# delay_panel.net
KiCad netlist of a schematic drawn in EAGLE
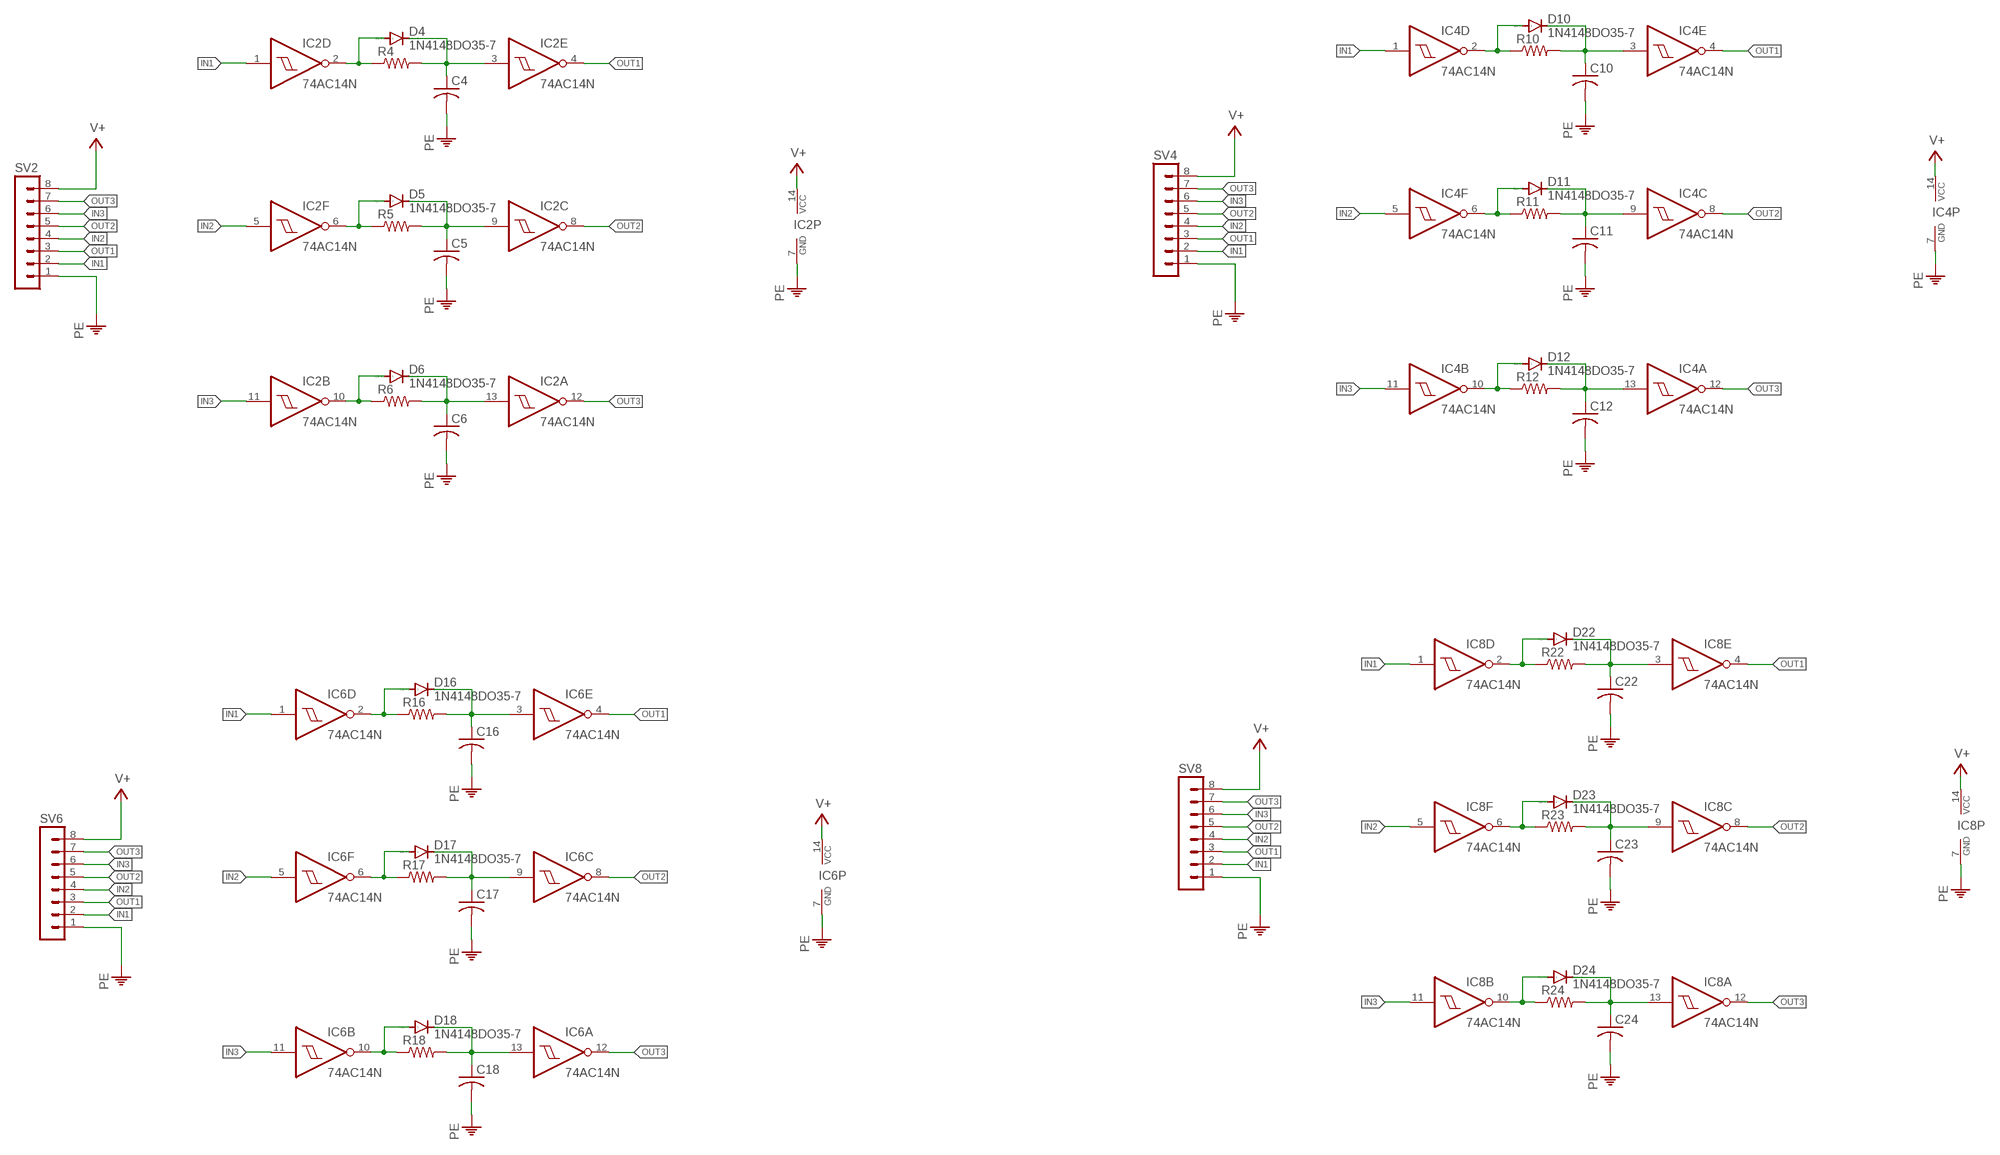
[diagram p0: schematic, sheet 1]

(export (version "E")
  (design (tool "Eeschema 10.0.6"))
  (components
    (comp (ref "C4")
      (value "C-US025-025X050")
      (footprint "eagle-import:C025-025X050")
      (libsource (lib "eagle-import") (part "C-US025-025X050"))
    )
    (comp (ref "C5")
      (value "C-US025-025X050")
      (footprint "eagle-import:C025-025X050")
      (libsource (lib "eagle-import") (part "C-US025-025X050"))
    )
    (comp (ref "C6")
      (value "C-US025-025X050")
      (footprint "eagle-import:C025-025X050")
      (libsource (lib "eagle-import") (part "C-US025-025X050"))
    )
    (comp (ref "C10")
      (value "C-US025-025X050")
      (footprint "eagle-import:C025-025X050")
      (libsource (lib "eagle-import") (part "C-US025-025X050"))
    )
    (comp (ref "C11")
      (value "C-US025-025X050")
      (footprint "eagle-import:C025-025X050")
      (libsource (lib "eagle-import") (part "C-US025-025X050"))
    )
    (comp (ref "C12")
      (value "C-US025-025X050")
      (footprint "eagle-import:C025-025X050")
      (libsource (lib "eagle-import") (part "C-US025-025X050"))
    )
    (comp (ref "C16")
      (value "C-US025-025X050")
      (footprint "eagle-import:C025-025X050")
      (libsource (lib "eagle-import") (part "C-US025-025X050"))
    )
    (comp (ref "C17")
      (value "C-US025-025X050")
      (footprint "eagle-import:C025-025X050")
      (libsource (lib "eagle-import") (part "C-US025-025X050"))
    )
    (comp (ref "C18")
      (value "C-US025-025X050")
      (footprint "eagle-import:C025-025X050")
      (libsource (lib "eagle-import") (part "C-US025-025X050"))
    )
    (comp (ref "C22")
      (value "C-US025-025X050")
      (footprint "eagle-import:C025-025X050")
      (libsource (lib "eagle-import") (part "C-US025-025X050"))
    )
    (comp (ref "C23")
      (value "C-US025-025X050")
      (footprint "eagle-import:C025-025X050")
      (libsource (lib "eagle-import") (part "C-US025-025X050"))
    )
    (comp (ref "C24")
      (value "C-US025-025X050")
      (footprint "eagle-import:C025-025X050")
      (libsource (lib "eagle-import") (part "C-US025-025X050"))
    )
    (comp (ref "D4")
      (value "1N4148DO35-7")
      (footprint "eagle-import:DO35-7")
      (libsource (lib "eagle-import") (part "1N4148DO35-7"))
    )
    (comp (ref "D5")
      (value "1N4148DO35-7")
      (footprint "eagle-import:DO35-7")
      (libsource (lib "eagle-import") (part "1N4148DO35-7"))
    )
    (comp (ref "D6")
      (value "1N4148DO35-7")
      (footprint "eagle-import:DO35-7")
      (libsource (lib "eagle-import") (part "1N4148DO35-7"))
    )
    (comp (ref "D10")
      (value "1N4148DO35-7")
      (footprint "eagle-import:DO35-7")
      (libsource (lib "eagle-import") (part "1N4148DO35-7"))
    )
    (comp (ref "D11")
      (value "1N4148DO35-7")
      (footprint "eagle-import:DO35-7")
      (libsource (lib "eagle-import") (part "1N4148DO35-7"))
    )
    (comp (ref "D12")
      (value "1N4148DO35-7")
      (footprint "eagle-import:DO35-7")
      (libsource (lib "eagle-import") (part "1N4148DO35-7"))
    )
    (comp (ref "D16")
      (value "1N4148DO35-7")
      (footprint "eagle-import:DO35-7")
      (libsource (lib "eagle-import") (part "1N4148DO35-7"))
    )
    (comp (ref "D17")
      (value "1N4148DO35-7")
      (footprint "eagle-import:DO35-7")
      (libsource (lib "eagle-import") (part "1N4148DO35-7"))
    )
    (comp (ref "D18")
      (value "1N4148DO35-7")
      (footprint "eagle-import:DO35-7")
      (libsource (lib "eagle-import") (part "1N4148DO35-7"))
    )
    (comp (ref "D22")
      (value "1N4148DO35-7")
      (footprint "eagle-import:DO35-7")
      (libsource (lib "eagle-import") (part "1N4148DO35-7"))
    )
    (comp (ref "D23")
      (value "1N4148DO35-7")
      (footprint "eagle-import:DO35-7")
      (libsource (lib "eagle-import") (part "1N4148DO35-7"))
    )
    (comp (ref "D24")
      (value "1N4148DO35-7")
      (footprint "eagle-import:DO35-7")
      (libsource (lib "eagle-import") (part "1N4148DO35-7"))
    )
    (comp (ref "IC2")
      (value "74AC14N")
      (footprint "eagle-import:DIL14")
      (libsource (lib "eagle-import") (part "7414NAC"))
    )
    (comp (ref "IC4")
      (value "74AC14N")
      (footprint "eagle-import:DIL14")
      (libsource (lib "eagle-import") (part "7414NAC"))
    )
    (comp (ref "IC6")
      (value "74AC14N")
      (footprint "eagle-import:DIL14")
      (libsource (lib "eagle-import") (part "7414NAC"))
    )
    (comp (ref "IC8")
      (value "74AC14N")
      (footprint "eagle-import:DIL14")
      (libsource (lib "eagle-import") (part "7414NAC"))
    )
    (comp (ref "R4")
      (value "R-US_0204/7")
      (footprint "eagle-import:0204_7")
      (libsource (lib "eagle-import") (part "R-US_0204/7"))
    )
    (comp (ref "R5")
      (value "R-US_0204/7")
      (footprint "eagle-import:0204_7")
      (libsource (lib "eagle-import") (part "R-US_0204/7"))
    )
    (comp (ref "R6")
      (value "R-US_0204/7")
      (footprint "eagle-import:0204_7")
      (libsource (lib "eagle-import") (part "R-US_0204/7"))
    )
    (comp (ref "R10")
      (value "R-US_0204/7")
      (footprint "eagle-import:0204_7")
      (libsource (lib "eagle-import") (part "R-US_0204/7"))
    )
    (comp (ref "R11")
      (value "R-US_0204/7")
      (footprint "eagle-import:0204_7")
      (libsource (lib "eagle-import") (part "R-US_0204/7"))
    )
    (comp (ref "R12")
      (value "R-US_0204/7")
      (footprint "eagle-import:0204_7")
      (libsource (lib "eagle-import") (part "R-US_0204/7"))
    )
    (comp (ref "R16")
      (value "R-US_0204/7")
      (footprint "eagle-import:0204_7")
      (libsource (lib "eagle-import") (part "R-US_0204/7"))
    )
    (comp (ref "R17")
      (value "R-US_0204/7")
      (footprint "eagle-import:0204_7")
      (libsource (lib "eagle-import") (part "R-US_0204/7"))
    )
    (comp (ref "R18")
      (value "R-US_0204/7")
      (footprint "eagle-import:0204_7")
      (libsource (lib "eagle-import") (part "R-US_0204/7"))
    )
    (comp (ref "R22")
      (value "R-US_0204/7")
      (footprint "eagle-import:0204_7")
      (libsource (lib "eagle-import") (part "R-US_0204/7"))
    )
    (comp (ref "R23")
      (value "R-US_0204/7")
      (footprint "eagle-import:0204_7")
      (libsource (lib "eagle-import") (part "R-US_0204/7"))
    )
    (comp (ref "R24")
      (value "R-US_0204/7")
      (footprint "eagle-import:0204_7")
      (libsource (lib "eagle-import") (part "R-US_0204/7"))
    )
    (comp (ref "SV2")
      (value "MA08-1")
      (footprint "eagle-import:MA08-1")
      (libsource (lib "eagle-import") (part "MA08-1"))
    )
    (comp (ref "SV4")
      (value "MA08-1")
      (footprint "eagle-import:MA08-1")
      (libsource (lib "eagle-import") (part "MA08-1"))
    )
    (comp (ref "SV6")
      (value "MA08-1")
      (footprint "eagle-import:MA08-1")
      (libsource (lib "eagle-import") (part "MA08-1"))
    )
    (comp (ref "SV8")
      (value "MA08-1")
      (footprint "eagle-import:MA08-1")
      (libsource (lib "eagle-import") (part "MA08-1"))
    )
  )
  (nets
    (net (code "1") (name "IN1") (class "Default")
      (node (ref "IC2") (pin "1") (pinfunction "I_1") (pintype "input"))
      (node (ref "IC4") (pin "1") (pinfunction "I_1") (pintype "input"))
      (node (ref "IC6") (pin "1") (pinfunction "I_1") (pintype "input"))
      (node (ref "IC8") (pin "1") (pinfunction "I_1") (pintype "input"))
      (node (ref "SV2") (pin "2") (pinfunction "2_2") (pintype "passive"))
      (node (ref "SV4") (pin "2") (pinfunction "2_2") (pintype "passive"))
      (node (ref "SV6") (pin "2") (pinfunction "2_2") (pintype "passive"))
      (node (ref "SV8") (pin "2") (pinfunction "2_2") (pintype "passive"))
    )
    (net (code "2") (name "IN2") (class "Default")
      (node (ref "IC2") (pin "5") (pinfunction "I_5") (pintype "input"))
      (node (ref "IC4") (pin "5") (pinfunction "I_5") (pintype "input"))
      (node (ref "IC6") (pin "5") (pinfunction "I_5") (pintype "input"))
      (node (ref "IC8") (pin "5") (pinfunction "I_5") (pintype "input"))
      (node (ref "SV2") (pin "4") (pinfunction "4_4") (pintype "passive"))
      (node (ref "SV4") (pin "4") (pinfunction "4_4") (pintype "passive"))
      (node (ref "SV6") (pin "4") (pinfunction "4_4") (pintype "passive"))
      (node (ref "SV8") (pin "4") (pinfunction "4_4") (pintype "passive"))
    )
    (net (code "3") (name "IN3") (class "Default")
      (node (ref "IC2") (pin "11") (pinfunction "I_11") (pintype "input"))
      (node (ref "IC4") (pin "11") (pinfunction "I_11") (pintype "input"))
      (node (ref "IC6") (pin "11") (pinfunction "I_11") (pintype "input"))
      (node (ref "IC8") (pin "11") (pinfunction "I_11") (pintype "input"))
      (node (ref "SV2") (pin "6") (pinfunction "6_6") (pintype "passive"))
      (node (ref "SV4") (pin "6") (pinfunction "6_6") (pintype "passive"))
      (node (ref "SV6") (pin "6") (pinfunction "6_6") (pintype "passive"))
      (node (ref "SV8") (pin "6") (pinfunction "6_6") (pintype "passive"))
    )
    (net (code "4") (name "Net-(IC2A-I)") (class "Default")
      (node (ref "C6") (pin "1") (pinfunction "1_1") (pintype "passive"))
      (node (ref "D6") (pin "C") (pinfunction "C_C") (pintype "passive"))
      (node (ref "IC2") (pin "13") (pinfunction "I_13") (pintype "input"))
      (node (ref "R6") (pin "2") (pinfunction "2_2") (pintype "passive"))
    )
    (net (code "5") (name "Net-(IC2B-O)") (class "Default")
      (node (ref "D6") (pin "A") (pinfunction "A_A") (pintype "passive"))
      (node (ref "IC2") (pin "10") (pinfunction "O_10") (pintype "output"))
      (node (ref "R6") (pin "1") (pinfunction "1_1") (pintype "passive"))
    )
    (net (code "6") (name "Net-(IC2C-I)") (class "Default")
      (node (ref "C5") (pin "1") (pinfunction "1_1") (pintype "passive"))
      (node (ref "D5") (pin "C") (pinfunction "C_C") (pintype "passive"))
      (node (ref "IC2") (pin "9") (pinfunction "I_9") (pintype "input"))
      (node (ref "R5") (pin "2") (pinfunction "2_2") (pintype "passive"))
    )
    (net (code "7") (name "Net-(IC2D-O)") (class "Default")
      (node (ref "D4") (pin "A") (pinfunction "A_A") (pintype "passive"))
      (node (ref "IC2") (pin "2") (pinfunction "O_2") (pintype "output"))
      (node (ref "R4") (pin "1") (pinfunction "1_1") (pintype "passive"))
    )
    (net (code "8") (name "Net-(IC2E-I)") (class "Default")
      (node (ref "C4") (pin "1") (pinfunction "1_1") (pintype "passive"))
      (node (ref "D4") (pin "C") (pinfunction "C_C") (pintype "passive"))
      (node (ref "IC2") (pin "3") (pinfunction "I_3") (pintype "input"))
      (node (ref "R4") (pin "2") (pinfunction "2_2") (pintype "passive"))
    )
    (net (code "9") (name "Net-(IC2F-O)") (class "Default")
      (node (ref "D5") (pin "A") (pinfunction "A_A") (pintype "passive"))
      (node (ref "IC2") (pin "6") (pinfunction "O_6") (pintype "output"))
      (node (ref "R5") (pin "1") (pinfunction "1_1") (pintype "passive"))
    )
    (net (code "10") (name "Net-(IC4A-I)") (class "Default")
      (node (ref "C12") (pin "1") (pinfunction "1_1") (pintype "passive"))
      (node (ref "D12") (pin "C") (pinfunction "C_C") (pintype "passive"))
      (node (ref "IC4") (pin "13") (pinfunction "I_13") (pintype "input"))
      (node (ref "R12") (pin "2") (pinfunction "2_2") (pintype "passive"))
    )
    (net (code "11") (name "Net-(IC4B-O)") (class "Default")
      (node (ref "D12") (pin "A") (pinfunction "A_A") (pintype "passive"))
      (node (ref "IC4") (pin "10") (pinfunction "O_10") (pintype "output"))
      (node (ref "R12") (pin "1") (pinfunction "1_1") (pintype "passive"))
    )
    (net (code "12") (name "Net-(IC4C-I)") (class "Default")
      (node (ref "C11") (pin "1") (pinfunction "1_1") (pintype "passive"))
      (node (ref "D11") (pin "C") (pinfunction "C_C") (pintype "passive"))
      (node (ref "IC4") (pin "9") (pinfunction "I_9") (pintype "input"))
      (node (ref "R11") (pin "2") (pinfunction "2_2") (pintype "passive"))
    )
    (net (code "13") (name "Net-(IC4D-O)") (class "Default")
      (node (ref "D10") (pin "A") (pinfunction "A_A") (pintype "passive"))
      (node (ref "IC4") (pin "2") (pinfunction "O_2") (pintype "output"))
      (node (ref "R10") (pin "1") (pinfunction "1_1") (pintype "passive"))
    )
    (net (code "14") (name "Net-(IC4E-I)") (class "Default")
      (node (ref "C10") (pin "1") (pinfunction "1_1") (pintype "passive"))
      (node (ref "D10") (pin "C") (pinfunction "C_C") (pintype "passive"))
      (node (ref "IC4") (pin "3") (pinfunction "I_3") (pintype "input"))
      (node (ref "R10") (pin "2") (pinfunction "2_2") (pintype "passive"))
    )
    (net (code "15") (name "Net-(IC4F-O)") (class "Default")
      (node (ref "D11") (pin "A") (pinfunction "A_A") (pintype "passive"))
      (node (ref "IC4") (pin "6") (pinfunction "O_6") (pintype "output"))
      (node (ref "R11") (pin "1") (pinfunction "1_1") (pintype "passive"))
    )
    (net (code "16") (name "Net-(IC6A-I)") (class "Default")
      (node (ref "C18") (pin "1") (pinfunction "1_1") (pintype "passive"))
      (node (ref "D18") (pin "C") (pinfunction "C_C") (pintype "passive"))
      (node (ref "IC6") (pin "13") (pinfunction "I_13") (pintype "input"))
      (node (ref "R18") (pin "2") (pinfunction "2_2") (pintype "passive"))
    )
    (net (code "17") (name "Net-(IC6B-O)") (class "Default")
      (node (ref "D18") (pin "A") (pinfunction "A_A") (pintype "passive"))
      (node (ref "IC6") (pin "10") (pinfunction "O_10") (pintype "output"))
      (node (ref "R18") (pin "1") (pinfunction "1_1") (pintype "passive"))
    )
    (net (code "18") (name "Net-(IC6C-I)") (class "Default")
      (node (ref "C17") (pin "1") (pinfunction "1_1") (pintype "passive"))
      (node (ref "D17") (pin "C") (pinfunction "C_C") (pintype "passive"))
      (node (ref "IC6") (pin "9") (pinfunction "I_9") (pintype "input"))
      (node (ref "R17") (pin "2") (pinfunction "2_2") (pintype "passive"))
    )
    (net (code "19") (name "Net-(IC6D-O)") (class "Default")
      (node (ref "D16") (pin "A") (pinfunction "A_A") (pintype "passive"))
      (node (ref "IC6") (pin "2") (pinfunction "O_2") (pintype "output"))
      (node (ref "R16") (pin "1") (pinfunction "1_1") (pintype "passive"))
    )
    (net (code "20") (name "Net-(IC6E-I)") (class "Default")
      (node (ref "C16") (pin "1") (pinfunction "1_1") (pintype "passive"))
      (node (ref "D16") (pin "C") (pinfunction "C_C") (pintype "passive"))
      (node (ref "IC6") (pin "3") (pinfunction "I_3") (pintype "input"))
      (node (ref "R16") (pin "2") (pinfunction "2_2") (pintype "passive"))
    )
    (net (code "21") (name "Net-(IC6F-O)") (class "Default")
      (node (ref "D17") (pin "A") (pinfunction "A_A") (pintype "passive"))
      (node (ref "IC6") (pin "6") (pinfunction "O_6") (pintype "output"))
      (node (ref "R17") (pin "1") (pinfunction "1_1") (pintype "passive"))
    )
    (net (code "22") (name "Net-(IC8A-I)") (class "Default")
      (node (ref "C24") (pin "1") (pinfunction "1_1") (pintype "passive"))
      (node (ref "D24") (pin "C") (pinfunction "C_C") (pintype "passive"))
      (node (ref "IC8") (pin "13") (pinfunction "I_13") (pintype "input"))
      (node (ref "R24") (pin "2") (pinfunction "2_2") (pintype "passive"))
    )
    (net (code "23") (name "Net-(IC8B-O)") (class "Default")
      (node (ref "D24") (pin "A") (pinfunction "A_A") (pintype "passive"))
      (node (ref "IC8") (pin "10") (pinfunction "O_10") (pintype "output"))
      (node (ref "R24") (pin "1") (pinfunction "1_1") (pintype "passive"))
    )
    (net (code "24") (name "Net-(IC8C-I)") (class "Default")
      (node (ref "C23") (pin "1") (pinfunction "1_1") (pintype "passive"))
      (node (ref "D23") (pin "C") (pinfunction "C_C") (pintype "passive"))
      (node (ref "IC8") (pin "9") (pinfunction "I_9") (pintype "input"))
      (node (ref "R23") (pin "2") (pinfunction "2_2") (pintype "passive"))
    )
    (net (code "25") (name "Net-(IC8D-O)") (class "Default")
      (node (ref "D22") (pin "A") (pinfunction "A_A") (pintype "passive"))
      (node (ref "IC8") (pin "2") (pinfunction "O_2") (pintype "output"))
      (node (ref "R22") (pin "1") (pinfunction "1_1") (pintype "passive"))
    )
    (net (code "26") (name "Net-(IC8E-I)") (class "Default")
      (node (ref "C22") (pin "1") (pinfunction "1_1") (pintype "passive"))
      (node (ref "D22") (pin "C") (pinfunction "C_C") (pintype "passive"))
      (node (ref "IC8") (pin "3") (pinfunction "I_3") (pintype "input"))
      (node (ref "R22") (pin "2") (pinfunction "2_2") (pintype "passive"))
    )
    (net (code "27") (name "Net-(IC8F-O)") (class "Default")
      (node (ref "D23") (pin "A") (pinfunction "A_A") (pintype "passive"))
      (node (ref "IC8") (pin "6") (pinfunction "O_6") (pintype "output"))
      (node (ref "R23") (pin "1") (pinfunction "1_1") (pintype "passive"))
    )
    (net (code "28") (name "OUT1") (class "Default")
      (node (ref "IC2") (pin "4") (pinfunction "O_4") (pintype "output"))
      (node (ref "IC4") (pin "4") (pinfunction "O_4") (pintype "output"))
      (node (ref "IC6") (pin "4") (pinfunction "O_4") (pintype "output"))
      (node (ref "IC8") (pin "4") (pinfunction "O_4") (pintype "output"))
      (node (ref "SV2") (pin "3") (pinfunction "3_3") (pintype "passive"))
      (node (ref "SV4") (pin "3") (pinfunction "3_3") (pintype "passive"))
      (node (ref "SV6") (pin "3") (pinfunction "3_3") (pintype "passive"))
      (node (ref "SV8") (pin "3") (pinfunction "3_3") (pintype "passive"))
    )
    (net (code "29") (name "OUT2") (class "Default")
      (node (ref "IC2") (pin "8") (pinfunction "O_8") (pintype "output"))
      (node (ref "IC4") (pin "8") (pinfunction "O_8") (pintype "output"))
      (node (ref "IC6") (pin "8") (pinfunction "O_8") (pintype "output"))
      (node (ref "IC8") (pin "8") (pinfunction "O_8") (pintype "output"))
      (node (ref "SV2") (pin "5") (pinfunction "5_5") (pintype "passive"))
      (node (ref "SV4") (pin "5") (pinfunction "5_5") (pintype "passive"))
      (node (ref "SV6") (pin "5") (pinfunction "5_5") (pintype "passive"))
      (node (ref "SV8") (pin "5") (pinfunction "5_5") (pintype "passive"))
    )
    (net (code "30") (name "OUT3") (class "Default")
      (node (ref "IC2") (pin "12") (pinfunction "O_12") (pintype "output"))
      (node (ref "IC4") (pin "12") (pinfunction "O_12") (pintype "output"))
      (node (ref "IC6") (pin "12") (pinfunction "O_12") (pintype "output"))
      (node (ref "IC8") (pin "12") (pinfunction "O_12") (pintype "output"))
      (node (ref "SV2") (pin "7") (pinfunction "7_7") (pintype "passive"))
      (node (ref "SV4") (pin "7") (pinfunction "7_7") (pintype "passive"))
      (node (ref "SV6") (pin "7") (pinfunction "7_7") (pintype "passive"))
      (node (ref "SV8") (pin "7") (pinfunction "7_7") (pintype "passive"))
    )
    (net (code "31") (name "PE") (class "Default")
      (node (ref "C10") (pin "2") (pinfunction "2_2") (pintype "passive"))
      (node (ref "C11") (pin "2") (pinfunction "2_2") (pintype "passive"))
      (node (ref "C12") (pin "2") (pinfunction "2_2") (pintype "passive"))
      (node (ref "C16") (pin "2") (pinfunction "2_2") (pintype "passive"))
      (node (ref "C17") (pin "2") (pinfunction "2_2") (pintype "passive"))
      (node (ref "C18") (pin "2") (pinfunction "2_2") (pintype "passive"))
      (node (ref "C22") (pin "2") (pinfunction "2_2") (pintype "passive"))
      (node (ref "C23") (pin "2") (pinfunction "2_2") (pintype "passive"))
      (node (ref "C24") (pin "2") (pinfunction "2_2") (pintype "passive"))
      (node (ref "C4") (pin "2") (pinfunction "2_2") (pintype "passive"))
      (node (ref "C5") (pin "2") (pinfunction "2_2") (pintype "passive"))
      (node (ref "C6") (pin "2") (pinfunction "2_2") (pintype "passive"))
      (node (ref "IC2") (pin "7") (pinfunction "GND_7") (pintype "power_in"))
      (node (ref "IC4") (pin "7") (pinfunction "GND_7") (pintype "power_in"))
      (node (ref "IC6") (pin "7") (pinfunction "GND_7") (pintype "power_in"))
      (node (ref "IC8") (pin "7") (pinfunction "GND_7") (pintype "power_in"))
      (node (ref "SV2") (pin "1") (pinfunction "1_1") (pintype "passive"))
      (node (ref "SV4") (pin "1") (pinfunction "1_1") (pintype "passive"))
      (node (ref "SV6") (pin "1") (pinfunction "1_1") (pintype "passive"))
      (node (ref "SV8") (pin "1") (pinfunction "1_1") (pintype "passive"))
    )
    (net (code "32") (name "V+") (class "Default")
      (node (ref "IC2") (pin "14") (pinfunction "VCC_14") (pintype "power_in"))
      (node (ref "IC4") (pin "14") (pinfunction "VCC_14") (pintype "power_in"))
      (node (ref "IC6") (pin "14") (pinfunction "VCC_14") (pintype "power_in"))
      (node (ref "IC8") (pin "14") (pinfunction "VCC_14") (pintype "power_in"))
      (node (ref "SV2") (pin "8") (pinfunction "8_8") (pintype "passive"))
      (node (ref "SV4") (pin "8") (pinfunction "8_8") (pintype "passive"))
      (node (ref "SV6") (pin "8") (pinfunction "8_8") (pintype "passive"))
      (node (ref "SV8") (pin "8") (pinfunction "8_8") (pintype "passive"))
    )
  )
)
